# am2067_4R_PCB.net
KiCad netlist of a schematic drawn in Altium Designer
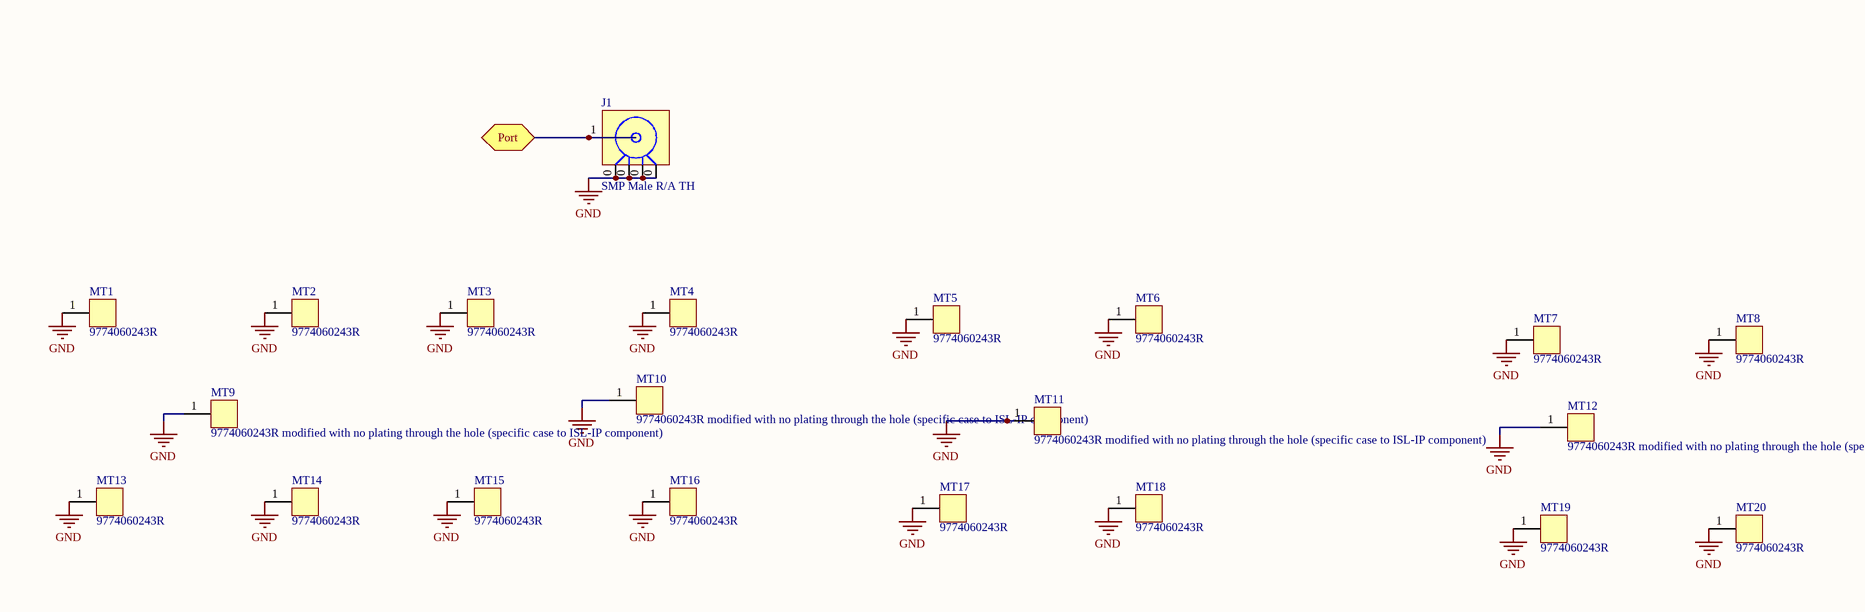
[diagram p0: am2067_4R_PCB.SchDoc, bottom left]

(export (version "E")
  (design (tool "Eeschema 10.0.6"))
  (components
    (comp (ref "J1")
      (value "SMP Male R/A TH")
      (footprint "SF1212-6000-TD")
      (description "SMP Male PCB Thru-Hole Connector, R/A, FD")
      (fields (field (name "MANUFACTURER") "Amphenol / SV Microwave"))
      (libsource (lib "GomSpace Vault") (part "COAX_5pin"))
    )
    (comp (ref "MT1")
      (value "9774060243R")
      (footprint "SMT_spacer_M2_6mm")
      (description "Pem nut, Surface Mount Nuts and Spacer, M2, 6mm")
      (fields (field (name "MANUFACTURER") "Wurth Electronik") (field (name "PART NUMBER") "SMTSO-M3-3ET"))
      (libsource (lib "GomSpace Vault") (part "MT_hole_1"))
    )
    (comp (ref "MT2")
      (value "9774060243R")
      (footprint "SMT_spacer_M2_6mm")
      (description "Pem nut, Surface Mount Nuts and Spacer, M2, 6mm")
      (fields (field (name "MANUFACTURER") "Wurth Electronik") (field (name "PART NUMBER") "SMTSO-M3-3ET"))
      (libsource (lib "GomSpace Vault") (part "MT_hole_1"))
    )
    (comp (ref "MT3")
      (value "9774060243R")
      (footprint "SMT_spacer_M2_6mm")
      (description "Pem nut, Surface Mount Nuts and Spacer, M2, 6mm")
      (fields (field (name "MANUFACTURER") "Wurth Electronik") (field (name "PART NUMBER") "SMTSO-M3-3ET"))
      (libsource (lib "GomSpace Vault") (part "MT_hole_1"))
    )
    (comp (ref "MT4")
      (value "9774060243R")
      (footprint "SMT_spacer_M2_6mm")
      (description "Pem nut, Surface Mount Nuts and Spacer, M2, 6mm")
      (fields (field (name "MANUFACTURER") "Wurth Electronik") (field (name "PART NUMBER") "SMTSO-M3-3ET"))
      (libsource (lib "GomSpace Vault") (part "MT_hole_1"))
    )
    (comp (ref "MT5")
      (value "9774060243R")
      (footprint "SMT_spacer_M2_6mm")
      (description "Pem nut, Surface Mount Nuts and Spacer, M2, 6mm")
      (fields (field (name "MANUFACTURER") "Wurth Electronik") (field (name "PART NUMBER") "SMTSO-M3-3ET"))
      (libsource (lib "GomSpace Vault") (part "MT_hole_1"))
    )
    (comp (ref "MT6")
      (value "9774060243R")
      (footprint "SMT_spacer_M2_6mm")
      (description "Pem nut, Surface Mount Nuts and Spacer, M2, 6mm")
      (fields (field (name "MANUFACTURER") "Wurth Electronik") (field (name "PART NUMBER") "SMTSO-M3-3ET"))
      (libsource (lib "GomSpace Vault") (part "MT_hole_1"))
    )
    (comp (ref "MT7")
      (value "9774060243R")
      (footprint "SMT_spacer_M2_6mm")
      (description "Pem nut, Surface Mount Nuts and Spacer, M2, 6mm")
      (fields (field (name "MANUFACTURER") "Wurth Electronik") (field (name "PART NUMBER") "SMTSO-M3-3ET"))
      (libsource (lib "GomSpace Vault") (part "MT_hole_1"))
    )
    (comp (ref "MT8")
      (value "9774060243R")
      (footprint "SMT_spacer_M2_6mm")
      (description "Pem nut, Surface Mount Nuts and Spacer, M2, 6mm")
      (fields (field (name "MANUFACTURER") "Wurth Electronik") (field (name "PART NUMBER") "SMTSO-M3-3ET"))
      (libsource (lib "GomSpace Vault") (part "MT_hole_1"))
    )
    (comp (ref "MT9")
      (value "9774060243R modified with no plating through the hole (specific case to ISL-IP component)")
      (footprint "SMT_spacer_M2_6mm differentiation with CMP-024-0033")
      (description "Pem nut, Surface Mount Nuts and Spacer, M2, 6mm")
      (fields (field (name "MANUFACTURER") "Wurth Electronik") (field (name "PART NUMBER") "SMTSO-M3-3ET"))
      (libsource (lib "GomSpace Vault") (part "MT_hole_1"))
    )
    (comp (ref "MT10")
      (value "9774060243R modified with no plating through the hole (specific case to ISL-IP component)")
      (footprint "SMT_spacer_M2_6mm differentiation with CMP-024-0033")
      (description "Pem nut, Surface Mount Nuts and Spacer, M2, 6mm")
      (fields (field (name "MANUFACTURER") "Wurth Electronik") (field (name "PART NUMBER") "SMTSO-M3-3ET"))
      (libsource (lib "GomSpace Vault") (part "MT_hole_1"))
    )
    (comp (ref "MT11")
      (value "9774060243R modified with no plating through the hole (specific case to ISL-IP component)")
      (footprint "SMT_spacer_M2_6mm differentiation with CMP-024-0033")
      (description "Pem nut, Surface Mount Nuts and Spacer, M2, 6mm")
      (fields (field (name "MANUFACTURER") "Wurth Electronik") (field (name "PART NUMBER") "SMTSO-M3-3ET"))
      (libsource (lib "GomSpace Vault") (part "MT_hole_1"))
    )
    (comp (ref "MT12")
      (value "9774060243R modified with no plating through the hole (specific case to ISL-IP component)")
      (footprint "SMT_spacer_M2_6mm differentiation with CMP-024-0033")
      (description "Pem nut, Surface Mount Nuts and Spacer, M2, 6mm")
      (fields (field (name "MANUFACTURER") "Wurth Electronik") (field (name "PART NUMBER") "SMTSO-M3-3ET"))
      (libsource (lib "GomSpace Vault") (part "MT_hole_1"))
    )
    (comp (ref "MT13")
      (value "9774060243R")
      (footprint "SMT_spacer_M2_6mm")
      (description "Pem nut, Surface Mount Nuts and Spacer, M2, 6mm")
      (fields (field (name "MANUFACTURER") "Wurth Electronik") (field (name "PART NUMBER") "SMTSO-M3-3ET"))
      (libsource (lib "GomSpace Vault") (part "MT_hole_1"))
    )
    (comp (ref "MT14")
      (value "9774060243R")
      (footprint "SMT_spacer_M2_6mm")
      (description "Pem nut, Surface Mount Nuts and Spacer, M2, 6mm")
      (fields (field (name "MANUFACTURER") "Wurth Electronik") (field (name "PART NUMBER") "SMTSO-M3-3ET"))
      (libsource (lib "GomSpace Vault") (part "MT_hole_1"))
    )
    (comp (ref "MT15")
      (value "9774060243R")
      (footprint "SMT_spacer_M2_6mm")
      (description "Pem nut, Surface Mount Nuts and Spacer, M2, 6mm")
      (fields (field (name "MANUFACTURER") "Wurth Electronik") (field (name "PART NUMBER") "SMTSO-M3-3ET"))
      (libsource (lib "GomSpace Vault") (part "MT_hole_1"))
    )
    (comp (ref "MT16")
      (value "9774060243R")
      (footprint "SMT_spacer_M2_6mm")
      (description "Pem nut, Surface Mount Nuts and Spacer, M2, 6mm")
      (fields (field (name "MANUFACTURER") "Wurth Electronik") (field (name "PART NUMBER") "SMTSO-M3-3ET"))
      (libsource (lib "GomSpace Vault") (part "MT_hole_1"))
    )
    (comp (ref "MT17")
      (value "9774060243R")
      (footprint "SMT_spacer_M2_6mm")
      (description "Pem nut, Surface Mount Nuts and Spacer, M2, 6mm")
      (fields (field (name "MANUFACTURER") "Wurth Electronik") (field (name "PART NUMBER") "SMTSO-M3-3ET"))
      (libsource (lib "GomSpace Vault") (part "MT_hole_1"))
    )
    (comp (ref "MT18")
      (value "9774060243R")
      (footprint "SMT_spacer_M2_6mm")
      (description "Pem nut, Surface Mount Nuts and Spacer, M2, 6mm")
      (fields (field (name "MANUFACTURER") "Wurth Electronik") (field (name "PART NUMBER") "SMTSO-M3-3ET"))
      (libsource (lib "GomSpace Vault") (part "MT_hole_1"))
    )
    (comp (ref "MT19")
      (value "9774060243R")
      (footprint "SMT_spacer_M2_6mm")
      (description "Pem nut, Surface Mount Nuts and Spacer, M2, 6mm")
      (fields (field (name "MANUFACTURER") "Wurth Electronik") (field (name "PART NUMBER") "SMTSO-M3-3ET"))
      (libsource (lib "GomSpace Vault") (part "MT_hole_1"))
    )
    (comp (ref "MT20")
      (value "9774060243R")
      (footprint "SMT_spacer_M2_6mm")
      (description "Pem nut, Surface Mount Nuts and Spacer, M2, 6mm")
      (fields (field (name "MANUFACTURER") "Wurth Electronik") (field (name "PART NUMBER") "SMTSO-M3-3ET"))
      (libsource (lib "GomSpace Vault") (part "MT_hole_1"))
    )
  )
  (nets
    (net (code "1") (name "/Port") (class "Default")
      (node (ref "J1") (pin "1") (pinfunction "1_1") (pintype "passive"))
    )
    (net (code "2") (name "GND") (class "Default")
      (node (ref "J1") (pin "0") (pinfunction "0_0") (pintype "power_in"))
      (node (ref "MT1") (pin "1") (pinfunction "1_1") (pintype "passive"))
      (node (ref "MT10") (pin "1") (pinfunction "1_1") (pintype "passive"))
      (node (ref "MT11") (pin "1") (pinfunction "1_1") (pintype "passive"))
      (node (ref "MT12") (pin "1") (pinfunction "1_1") (pintype "passive"))
      (node (ref "MT13") (pin "1") (pinfunction "1_1") (pintype "passive"))
      (node (ref "MT14") (pin "1") (pinfunction "1_1") (pintype "passive"))
      (node (ref "MT15") (pin "1") (pinfunction "1_1") (pintype "passive"))
      (node (ref "MT16") (pin "1") (pinfunction "1_1") (pintype "passive"))
      (node (ref "MT17") (pin "1") (pinfunction "1_1") (pintype "passive"))
      (node (ref "MT18") (pin "1") (pinfunction "1_1") (pintype "passive"))
      (node (ref "MT19") (pin "1") (pinfunction "1_1") (pintype "passive"))
      (node (ref "MT2") (pin "1") (pinfunction "1_1") (pintype "passive"))
      (node (ref "MT20") (pin "1") (pinfunction "1_1") (pintype "passive"))
      (node (ref "MT3") (pin "1") (pinfunction "1_1") (pintype "passive"))
      (node (ref "MT4") (pin "1") (pinfunction "1_1") (pintype "passive"))
      (node (ref "MT5") (pin "1") (pinfunction "1_1") (pintype "passive"))
      (node (ref "MT6") (pin "1") (pinfunction "1_1") (pintype "passive"))
      (node (ref "MT7") (pin "1") (pinfunction "1_1") (pintype "passive"))
      (node (ref "MT8") (pin "1") (pinfunction "1_1") (pintype "passive"))
      (node (ref "MT9") (pin "1") (pinfunction "1_1") (pintype "passive"))
    )
  )
)
